# Tds_NonSmd_PRINT.net
KiCad netlist of a schematic drawn in EAGLE
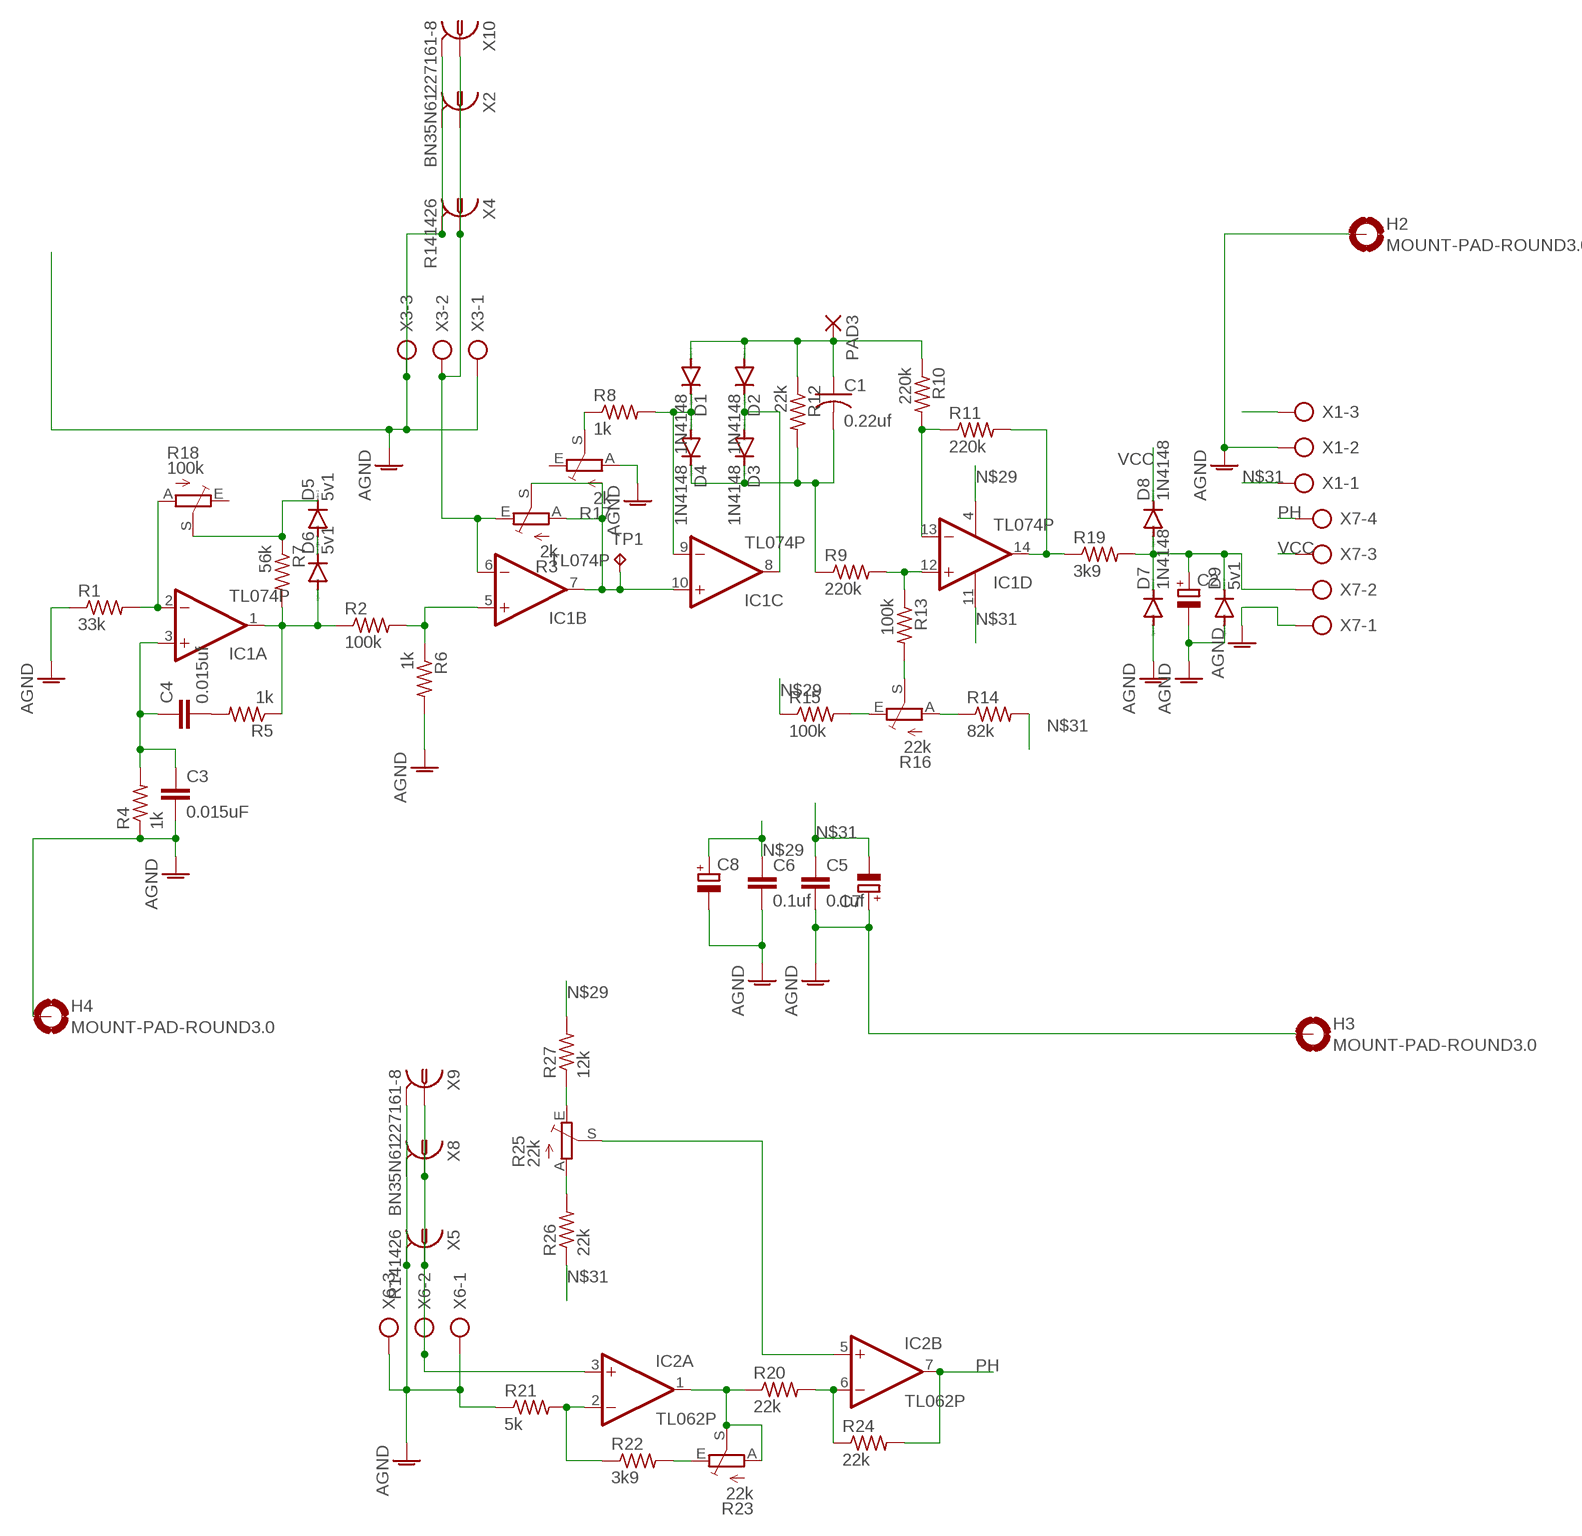
[diagram p0: schematic, sheet 1]

(export (version "E")
  (design (tool "Eeschema 10.0.6"))
  (components
    (comp (ref "C1")
      (value "0.22uf")
      (footprint "eagle-import:C050-024X044")
      (libsource (lib "eagle-import") (part "C-US050-024X044"))
    )
    (comp (ref "C2")
      (value "CPOL-EUE5-8.5")
      (footprint "eagle-import:E5-8,5")
      (libsource (lib "eagle-import") (part "CPOL-EUE5-8.5"))
    )
    (comp (ref "C3")
      (value "0.015uF")
      (footprint "eagle-import:C050-024X044")
      (libsource (lib "eagle-import") (part "C-EU050-024X044"))
    )
    (comp (ref "C4")
      (value "0.015uf")
      (footprint "eagle-import:C050-024X044")
      (libsource (lib "eagle-import") (part "C-EU050-024X044"))
    )
    (comp (ref "C5")
      (value "0.1uf")
      (footprint "eagle-import:C5B2.5")
      (libsource (lib "eagle-import") (part "C5/2.5"))
    )
    (comp (ref "C6")
      (value "0.1uf")
      (footprint "eagle-import:C5B2.5")
      (libsource (lib "eagle-import") (part "C5/2.5"))
    )
    (comp (ref "C7")
      (value "CPOL-EUE5-8.5")
      (footprint "eagle-import:E5-8,5")
      (libsource (lib "eagle-import") (part "CPOL-EUE5-8.5"))
    )
    (comp (ref "C8")
      (value "CPOL-EUE5-8.5")
      (footprint "eagle-import:E5-8,5")
      (libsource (lib "eagle-import") (part "CPOL-EUE5-8.5"))
    )
    (comp (ref "D1")
      (value "1N4148")
      (footprint "eagle-import:DO35-7")
      (libsource (lib "eagle-import") (part "1N4148DO35-7"))
    )
    (comp (ref "D2")
      (value "1N4148")
      (footprint "eagle-import:DO35-7")
      (libsource (lib "eagle-import") (part "1N4148DO35-7"))
    )
    (comp (ref "D3")
      (value "1N4148")
      (footprint "eagle-import:DO35-7")
      (libsource (lib "eagle-import") (part "1N4148DO35-7"))
    )
    (comp (ref "D4")
      (value "1N4148")
      (footprint "eagle-import:DO35-7")
      (libsource (lib "eagle-import") (part "1N4148DO35-7"))
    )
    (comp (ref "D5")
      (value "5v1")
      (footprint "eagle-import:DO35-7")
      (libsource (lib "eagle-import") (part "1N4148DO35-7"))
    )
    (comp (ref "D6")
      (value "5v1")
      (footprint "eagle-import:DO35-7")
      (libsource (lib "eagle-import") (part "1N4148DO35-7"))
    )
    (comp (ref "D7")
      (value "1N4148")
      (footprint "eagle-import:DO35-7")
      (libsource (lib "eagle-import") (part "1N4148DO35-7"))
    )
    (comp (ref "D8")
      (value "1N4148")
      (footprint "eagle-import:DO35-7")
      (libsource (lib "eagle-import") (part "1N4148DO35-7"))
    )
    (comp (ref "D9")
      (value "5v1")
      (footprint "eagle-import:DO35-7")
      (libsource (lib "eagle-import") (part "1N4148DO35-7"))
    )
    (comp (ref "H2")
      (value "MOUNT-PAD-ROUND3.0")
      (footprint "eagle-import:3,0-PAD")
      (libsource (lib "eagle-import") (part "MOUNT-PAD-ROUND3.0"))
    )
    (comp (ref "H3")
      (value "MOUNT-PAD-ROUND3.0")
      (footprint "eagle-import:3,0-PAD")
      (libsource (lib "eagle-import") (part "MOUNT-PAD-ROUND3.0"))
    )
    (comp (ref "H4")
      (value "MOUNT-PAD-ROUND3.0")
      (footprint "eagle-import:3,0-PAD")
      (libsource (lib "eagle-import") (part "MOUNT-PAD-ROUND3.0"))
    )
    (comp (ref "IC1")
      (value "TL074P")
      (footprint "eagle-import:DIL14")
      (libsource (lib "eagle-import") (part "TL074P"))
    )
    (comp (ref "IC2")
      (value "TL062P")
      (footprint "eagle-import:DIL08")
      (libsource (lib "eagle-import") (part "TL062P"))
    )
    (comp (ref "PAD3")
      (value "2,54/1,1")
      (footprint "eagle-import:2,54_1,1")
      (libsource (lib "eagle-import") (part "2,54/1,1"))
    )
    (comp (ref "R1")
      (value "33k")
      (footprint "eagle-import:0207_7")
      (libsource (lib "eagle-import") (part "resistor_348_R-US_0207/7"))
    )
    (comp (ref "R2")
      (value "100k")
      (footprint "eagle-import:0207_10")
      (libsource (lib "eagle-import") (part "R-US_0207/10"))
    )
    (comp (ref "R3")
      (value "2k")
      (footprint "eagle-import:S64W")
      (libsource (lib "eagle-import") (part "TRIM_EU-S64W"))
    )
    (comp (ref "R4")
      (value "1k")
      (footprint "eagle-import:0207_7")
      (libsource (lib "eagle-import") (part "resistor_348_R-US_0207/7"))
    )
    (comp (ref "R5")
      (value "1k")
      (footprint "eagle-import:0207_7")
      (libsource (lib "eagle-import") (part "resistor_348_R-US_0207/7"))
    )
    (comp (ref "R6")
      (value "1k")
      (footprint "eagle-import:0207_7")
      (libsource (lib "eagle-import") (part "resistor_348_R-US_0207/7"))
    )
    (comp (ref "R7")
      (value "56k")
      (footprint "eagle-import:0207_7")
      (libsource (lib "eagle-import") (part "resistor_348_R-US_0207/7"))
    )
    (comp (ref "R8")
      (value "1k")
      (footprint "eagle-import:0207_7")
      (libsource (lib "eagle-import") (part "resistor_348_R-US_0207/7"))
    )
    (comp (ref "R9")
      (value "220k")
      (footprint "eagle-import:0207_7")
      (libsource (lib "eagle-import") (part "resistor_348_R-US_0207/7"))
    )
    (comp (ref "R10")
      (value "220k")
      (footprint "eagle-import:0207_7")
      (libsource (lib "eagle-import") (part "resistor_348_R-US_0207/7"))
    )
    (comp (ref "R11")
      (value "220k")
      (footprint "eagle-import:0207_7")
      (libsource (lib "eagle-import") (part "resistor_348_R-US_0207/7"))
    )
    (comp (ref "R12")
      (value "22k")
      (footprint "eagle-import:0207_7")
      (libsource (lib "eagle-import") (part "resistor_348_R-US_0207/7"))
    )
    (comp (ref "R13")
      (value "100k")
      (footprint "eagle-import:0207_7")
      (libsource (lib "eagle-import") (part "resistor_348_R-US_0207/7"))
    )
    (comp (ref "R14")
      (value "82k")
      (footprint "eagle-import:0207_7")
      (libsource (lib "eagle-import") (part "resistor_348_R-US_0207/7"))
    )
    (comp (ref "R15")
      (value "100k")
      (footprint "eagle-import:0207_7")
      (libsource (lib "eagle-import") (part "resistor_348_R-US_0207/7"))
    )
    (comp (ref "R16")
      (value "22k")
      (footprint "eagle-import:S64W")
      (libsource (lib "eagle-import") (part "TRIM_EU-S64W"))
    )
    (comp (ref "R17")
      (value "2k")
      (footprint "eagle-import:S64W")
      (libsource (lib "eagle-import") (part "TRIM_EU-S64W"))
    )
    (comp (ref "R18")
      (value "100k")
      (footprint "eagle-import:S64W")
      (libsource (lib "eagle-import") (part "TRIM_EU-S64W"))
    )
    (comp (ref "R19")
      (value "3k9")
      (footprint "eagle-import:0207_7")
      (libsource (lib "eagle-import") (part "resistor_348_R-US_0207/7"))
    )
    (comp (ref "R20")
      (value "22k")
      (footprint "eagle-import:0207_7")
      (libsource (lib "eagle-import") (part "resistor_348_R-US_0207/7"))
    )
    (comp (ref "R21")
      (value "5k")
      (footprint "eagle-import:0207_7")
      (libsource (lib "eagle-import") (part "resistor_348_R-US_0207/7"))
    )
    (comp (ref "R22")
      (value "3k9")
      (footprint "eagle-import:0207_7")
      (libsource (lib "eagle-import") (part "resistor_348_R-US_0207/7"))
    )
    (comp (ref "R23")
      (value "22k")
      (footprint "eagle-import:S64W")
      (libsource (lib "eagle-import") (part "TRIM_EU-S64W"))
    )
    (comp (ref "R24")
      (value "22k")
      (footprint "eagle-import:0207_7")
      (libsource (lib "eagle-import") (part "resistor_348_R-US_0207/7"))
    )
    (comp (ref "R25")
      (value "22k")
      (footprint "eagle-import:S64W")
      (libsource (lib "eagle-import") (part "TRIM_EU-S64W"))
    )
    (comp (ref "R26")
      (value "22k")
      (footprint "eagle-import:0207_7")
      (libsource (lib "eagle-import") (part "resistor_348_R-US_0207/7"))
    )
    (comp (ref "R27")
      (value "12k")
      (footprint "eagle-import:0207_7")
      (libsource (lib "eagle-import") (part "resistor_348_R-US_0207/7"))
    )
    (comp (ref "TP1")
      (value "TPPAD1-13")
      (footprint "eagle-import:P1-13")
      (libsource (lib "eagle-import") (part "TPPAD1-13"))
    )
    (comp (ref "X1")
      (value "AK500/3")
      (footprint "eagle-import:AK500_3")
      (libsource (lib "eagle-import") (part "AK500/3"))
    )
    (comp (ref "X2")
      (value "BN35N61")
      (footprint "eagle-import:B35N61")
      (libsource (lib "eagle-import") (part "BN35N61"))
    )
    (comp (ref "X3")
      (value "AK500/3")
      (footprint "eagle-import:AK500_3")
      (libsource (lib "eagle-import") (part "AK500/3"))
    )
    (comp (ref "X4")
      (value "R141426")
      (footprint "eagle-import:R141426")
      (fields (field (name "MF") "FARNELL") (field (name "MPN") "R141426161"))
      (libsource (lib "eagle-import") (part "R141426"))
    )
    (comp (ref "X5")
      (value "R141426")
      (footprint "eagle-import:R141426")
      (fields (field (name "MF") "FARNELL") (field (name "MPN") "R141426161"))
      (libsource (lib "eagle-import") (part "R141426"))
    )
    (comp (ref "X6")
      (value "AK500/3")
      (footprint "eagle-import:AK500_3")
      (libsource (lib "eagle-import") (part "AK500/3"))
    )
    (comp (ref "X7")
      (value "AK500/4")
      (footprint "eagle-import:AK500_4")
      (libsource (lib "eagle-import") (part "AK500/4"))
    )
    (comp (ref "X8")
      (value "BN35N61")
      (footprint "eagle-import:B35N61")
      (libsource (lib "eagle-import") (part "BN35N61"))
    )
    (comp (ref "X9")
      (value "227161-8")
      (footprint "eagle-import:AMP_227161")
      (libsource (lib "eagle-import") (part "?227161-8"))
    )
    (comp (ref "X10")
      (value "227161-8")
      (footprint "eagle-import:AMP_227161")
      (libsource (lib "eagle-import") (part "?227161-8"))
    )
  )
  (nets
    (net (code "1") (name "/N$29") (class "Default")
      (node (ref "C6") (pin "1") (pinfunction "1_1") (pintype "passive"))
      (node (ref "C8") (pin "+") (pinfunction "+_+") (pintype "passive"))
      (node (ref "IC1") (pin "4") (pinfunction "V+_4") (pintype "power_in"))
      (node (ref "R15") (pin "1") (pinfunction "1_1") (pintype "passive"))
      (node (ref "R27") (pin "2") (pinfunction "2_2") (pintype "passive"))
      (node (ref "X1") (pin "3") (pinfunction "KL_3") (pintype "passive"))
    )
    (net (code "2") (name "/N$31") (class "Default")
      (node (ref "C5") (pin "1") (pinfunction "1_1") (pintype "passive"))
      (node (ref "C7") (pin "-") (pinfunction "-_-") (pintype "passive"))
      (node (ref "IC1") (pin "11") (pinfunction "V-_11") (pintype "power_in"))
      (node (ref "R14") (pin "2") (pinfunction "2_2") (pintype "passive"))
      (node (ref "R26") (pin "1") (pinfunction "1_1") (pintype "passive"))
      (node (ref "X1") (pin "1") (pinfunction "KL_1") (pintype "passive"))
    )
    (net (code "3") (name "/PH") (class "Default")
      (node (ref "IC2") (pin "7") (pinfunction "OUT_7") (pintype "output"))
      (node (ref "R24") (pin "2") (pinfunction "2_2") (pintype "passive"))
      (node (ref "X7") (pin "4") (pinfunction "KL_4") (pintype "passive"))
    )
    (net (code "4") (name "/VCC") (class "Default")
      (node (ref "D8") (pin "C") (pinfunction "C_C") (pintype "passive"))
      (node (ref "X7") (pin "3") (pinfunction "KL_3") (pintype "passive"))
    )
    (net (code "5") (name "AGND") (class "Default")
      (node (ref "C2") (pin "-") (pinfunction "-_-") (pintype "passive"))
      (node (ref "C3") (pin "2") (pinfunction "2_2") (pintype "passive"))
      (node (ref "C5") (pin "2") (pinfunction "2_2") (pintype "passive"))
      (node (ref "C6") (pin "2") (pinfunction "2_2") (pintype "passive"))
      (node (ref "C7") (pin "+") (pinfunction "+_+") (pintype "passive"))
      (node (ref "C8") (pin "-") (pinfunction "-_-") (pintype "passive"))
      (node (ref "D7") (pin "A") (pinfunction "A_A") (pintype "passive"))
      (node (ref "D9") (pin "A") (pinfunction "A_A") (pintype "passive"))
      (node (ref "H2") (pin "B3,0") (pinfunction "MOUNT_B3,0") (pintype "passive"))
      (node (ref "H3") (pin "B3,0") (pinfunction "MOUNT_B3,0") (pintype "passive"))
      (node (ref "H4") (pin "B3,0") (pinfunction "MOUNT_B3,0") (pintype "passive"))
      (node (ref "R1") (pin "1") (pinfunction "1_1") (pintype "passive"))
      (node (ref "R17") (pin "A") (pinfunction "A_A") (pintype "passive"))
      (node (ref "R21") (pin "1") (pinfunction "1_1") (pintype "passive"))
      (node (ref "R4") (pin "1") (pinfunction "1_1") (pintype "passive"))
      (node (ref "R6") (pin "2") (pinfunction "2_2") (pintype "passive"))
      (node (ref "X1") (pin "2") (pinfunction "KL_2") (pintype "passive"))
      (node (ref "X10") (pin "2") (pinfunction "2_2") (pintype "passive"))
      (node (ref "X2") (pin "2") (pinfunction "2_2") (pintype "passive"))
      (node (ref "X2") (pin "3") (pinfunction "2_3") (pintype "passive"))
      (node (ref "X2") (pin "4") (pinfunction "2_4") (pintype "passive"))
      (node (ref "X2") (pin "5") (pinfunction "2_5") (pintype "passive"))
      (node (ref "X3") (pin "1") (pinfunction "KL_1") (pintype "passive"))
      (node (ref "X3") (pin "3") (pinfunction "KL_3") (pintype "passive"))
      (node (ref "X4") (pin "2") (pinfunction "2_2") (pintype "passive"))
      (node (ref "X4") (pin "3") (pinfunction "2_3") (pintype "passive"))
      (node (ref "X4") (pin "4") (pinfunction "2_4") (pintype "passive"))
      (node (ref "X4") (pin "5") (pinfunction "2_5") (pintype "passive"))
      (node (ref "X5") (pin "2") (pinfunction "2_2") (pintype "passive"))
      (node (ref "X5") (pin "3") (pinfunction "2_3") (pintype "passive"))
      (node (ref "X5") (pin "4") (pinfunction "2_4") (pintype "passive"))
      (node (ref "X5") (pin "5") (pinfunction "2_5") (pintype "passive"))
      (node (ref "X6") (pin "1") (pinfunction "KL_1") (pintype "passive"))
      (node (ref "X6") (pin "3") (pinfunction "KL_3") (pintype "passive"))
      (node (ref "X7") (pin "1") (pinfunction "KL_1") (pintype "passive"))
      (node (ref "X8") (pin "2") (pinfunction "2_2") (pintype "passive"))
      (node (ref "X8") (pin "3") (pinfunction "2_3") (pintype "passive"))
      (node (ref "X8") (pin "4") (pinfunction "2_4") (pintype "passive"))
      (node (ref "X8") (pin "5") (pinfunction "2_5") (pintype "passive"))
      (node (ref "X9") (pin "2") (pinfunction "2_2") (pintype "passive"))
    )
    (net (code "6") (name "Net-(C1-Pad2)") (class "Default")
      (node (ref "C1") (pin "2") (pinfunction "2_2") (pintype "passive"))
      (node (ref "D3") (pin "C") (pinfunction "C_C") (pintype "passive"))
      (node (ref "D4") (pin "C") (pinfunction "C_C") (pintype "passive"))
      (node (ref "R12") (pin "2") (pinfunction "2_2") (pintype "passive"))
      (node (ref "R9") (pin "1") (pinfunction "1_1") (pintype "passive"))
    )
    (net (code "7") (name "Net-(C4-Pad2)") (class "Default")
      (node (ref "C4") (pin "2") (pinfunction "2_2") (pintype "passive"))
      (node (ref "R5") (pin "2") (pinfunction "2_2") (pintype "passive"))
    )
    (net (code "8") (name "Net-(D5-PadA)") (class "Default")
      (node (ref "D5") (pin "A") (pinfunction "A_A") (pintype "passive"))
      (node (ref "D6") (pin "C") (pinfunction "C_C") (pintype "passive"))
    )
    (net (code "9") (name "Net-(D5-PadC)") (class "Default")
      (node (ref "D5") (pin "C") (pinfunction "C_C") (pintype "passive"))
      (node (ref "R18") (pin "S") (pinfunction "S_S") (pintype "passive"))
      (node (ref "R7") (pin "1") (pinfunction "1_1") (pintype "passive"))
    )
    (net (code "10") (name "Net-(IC1A-+IN)") (class "Default")
      (node (ref "C3") (pin "1") (pinfunction "1_1") (pintype "passive"))
      (node (ref "C4") (pin "1") (pinfunction "1_1") (pintype "passive"))
      (node (ref "IC1") (pin "3") (pinfunction "+IN_3") (pintype "input"))
      (node (ref "R4") (pin "2") (pinfunction "2_2") (pintype "passive"))
    )
    (net (code "11") (name "Net-(IC1A--IN)") (class "Default")
      (node (ref "IC1") (pin "2") (pinfunction "-IN_2") (pintype "input"))
      (node (ref "R1") (pin "2") (pinfunction "2_2") (pintype "passive"))
      (node (ref "R18") (pin "A") (pinfunction "A_A") (pintype "passive"))
    )
    (net (code "12") (name "Net-(IC1A-OUT)") (class "Default")
      (node (ref "D6") (pin "A") (pinfunction "A_A") (pintype "passive"))
      (node (ref "IC1") (pin "1") (pinfunction "OUT_1") (pintype "output"))
      (node (ref "R2") (pin "1") (pinfunction "1_1") (pintype "passive"))
      (node (ref "R5") (pin "1") (pinfunction "1_1") (pintype "passive"))
      (node (ref "R7") (pin "2") (pinfunction "2_2") (pintype "passive"))
    )
    (net (code "13") (name "Net-(IC1B-+IN)") (class "Default")
      (node (ref "IC1") (pin "5") (pinfunction "+IN_5") (pintype "input"))
      (node (ref "R2") (pin "2") (pinfunction "2_2") (pintype "passive"))
      (node (ref "R6") (pin "1") (pinfunction "1_1") (pintype "passive"))
    )
    (net (code "14") (name "Net-(IC1B--IN)") (class "Default")
      (node (ref "IC1") (pin "6") (pinfunction "-IN_6") (pintype "input"))
      (node (ref "R3") (pin "E") (pinfunction "E_E") (pintype "passive"))
      (node (ref "X10") (pin "1") (pinfunction "1_1") (pintype "passive"))
      (node (ref "X2") (pin "1") (pinfunction "1_1") (pintype "passive"))
      (node (ref "X3") (pin "2") (pinfunction "KL_2") (pintype "passive"))
      (node (ref "X4") (pin "1") (pinfunction "1_1") (pintype "passive"))
    )
    (net (code "15") (name "Net-(IC1B-OUT)") (class "Default")
      (node (ref "IC1") (pin "10") (pinfunction "+IN_10") (pintype "input"))
      (node (ref "IC1") (pin "7") (pinfunction "OUT_7") (pintype "output"))
      (node (ref "R3") (pin "A") (pinfunction "A_A") (pintype "passive"))
      (node (ref "R3") (pin "S") (pinfunction "S_S") (pintype "passive"))
      (node (ref "TP1") (pin "TP") (pinfunction "TP_TP") (pintype "input"))
    )
    (net (code "16") (name "Net-(IC1C--IN)") (class "Default")
      (node (ref "D1") (pin "C") (pinfunction "C_C") (pintype "passive"))
      (node (ref "D4") (pin "A") (pinfunction "A_A") (pintype "passive"))
      (node (ref "IC1") (pin "9") (pinfunction "-IN_9") (pintype "input"))
      (node (ref "R8") (pin "2") (pinfunction "2_2") (pintype "passive"))
    )
    (net (code "17") (name "Net-(IC1C-OUT)") (class "Default")
      (node (ref "D2") (pin "C") (pinfunction "C_C") (pintype "passive"))
      (node (ref "D3") (pin "A") (pinfunction "A_A") (pintype "passive"))
      (node (ref "IC1") (pin "8") (pinfunction "OUT_8") (pintype "output"))
    )
    (net (code "18") (name "Net-(IC1D-+IN)") (class "Default")
      (node (ref "IC1") (pin "12") (pinfunction "+IN_12") (pintype "input"))
      (node (ref "R13") (pin "1") (pinfunction "1_1") (pintype "passive"))
      (node (ref "R9") (pin "2") (pinfunction "2_2") (pintype "passive"))
    )
    (net (code "19") (name "Net-(IC1D--IN)") (class "Default")
      (node (ref "IC1") (pin "13") (pinfunction "-IN_13") (pintype "input"))
      (node (ref "R10") (pin "2") (pinfunction "2_2") (pintype "passive"))
      (node (ref "R11") (pin "1") (pinfunction "1_1") (pintype "passive"))
    )
    (net (code "20") (name "Net-(IC1D-OUT)") (class "Default")
      (node (ref "IC1") (pin "14") (pinfunction "OUT_14") (pintype "output"))
      (node (ref "R11") (pin "2") (pinfunction "2_2") (pintype "passive"))
      (node (ref "R19") (pin "1") (pinfunction "1_1") (pintype "passive"))
    )
    (net (code "21") (name "Net-(IC2A-+IN)") (class "Default")
      (node (ref "IC2") (pin "3") (pinfunction "+IN_3") (pintype "input"))
      (node (ref "X5") (pin "1") (pinfunction "1_1") (pintype "passive"))
      (node (ref "X6") (pin "2") (pinfunction "KL_2") (pintype "passive"))
      (node (ref "X8") (pin "1") (pinfunction "1_1") (pintype "passive"))
      (node (ref "X9") (pin "1") (pinfunction "1_1") (pintype "passive"))
    )
    (net (code "22") (name "Net-(IC2A--IN)") (class "Default")
      (node (ref "IC2") (pin "2") (pinfunction "-IN_2") (pintype "input"))
      (node (ref "R21") (pin "2") (pinfunction "2_2") (pintype "passive"))
      (node (ref "R22") (pin "1") (pinfunction "1_1") (pintype "passive"))
    )
    (net (code "23") (name "Net-(IC2A-OUT)") (class "Default")
      (node (ref "IC2") (pin "1") (pinfunction "OUT_1") (pintype "output"))
      (node (ref "R20") (pin "1") (pinfunction "1_1") (pintype "passive"))
      (node (ref "R23") (pin "A") (pinfunction "A_A") (pintype "passive"))
      (node (ref "R23") (pin "S") (pinfunction "S_S") (pintype "passive"))
    )
    (net (code "24") (name "Net-(IC2B-+IN)") (class "Default")
      (node (ref "IC2") (pin "5") (pinfunction "+IN_5") (pintype "input"))
      (node (ref "R25") (pin "S") (pinfunction "S_S") (pintype "passive"))
    )
    (net (code "25") (name "Net-(IC2B--IN)") (class "Default")
      (node (ref "IC2") (pin "6") (pinfunction "-IN_6") (pintype "input"))
      (node (ref "R20") (pin "2") (pinfunction "2_2") (pintype "passive"))
      (node (ref "R24") (pin "1") (pinfunction "1_1") (pintype "passive"))
    )
    (net (code "26") (name "Net-(PAD3-P)") (class "Default")
      (node (ref "C1") (pin "1") (pinfunction "1_1") (pintype "passive"))
      (node (ref "D1") (pin "A") (pinfunction "A_A") (pintype "passive"))
      (node (ref "D2") (pin "A") (pinfunction "A_A") (pintype "passive"))
      (node (ref "PAD3") (pin "1") (pinfunction "P_1") (pintype "passive"))
      (node (ref "R10") (pin "1") (pinfunction "1_1") (pintype "passive"))
      (node (ref "R12") (pin "1") (pinfunction "1_1") (pintype "passive"))
    )
    (net (code "27") (name "Net-(R13-Pad2)") (class "Default")
      (node (ref "R13") (pin "2") (pinfunction "2_2") (pintype "passive"))
      (node (ref "R16") (pin "S") (pinfunction "S_S") (pintype "passive"))
    )
    (net (code "28") (name "Net-(R14-Pad1)") (class "Default")
      (node (ref "R14") (pin "1") (pinfunction "1_1") (pintype "passive"))
      (node (ref "R16") (pin "A") (pinfunction "A_A") (pintype "passive"))
    )
    (net (code "29") (name "Net-(R15-Pad2)") (class "Default")
      (node (ref "R15") (pin "2") (pinfunction "2_2") (pintype "passive"))
      (node (ref "R16") (pin "E") (pinfunction "E_E") (pintype "passive"))
    )
    (net (code "30") (name "Net-(R17-PadS)") (class "Default")
      (node (ref "R17") (pin "S") (pinfunction "S_S") (pintype "passive"))
      (node (ref "R8") (pin "1") (pinfunction "1_1") (pintype "passive"))
    )
    (net (code "31") (name "Net-(R22-Pad2)") (class "Default")
      (node (ref "R22") (pin "2") (pinfunction "2_2") (pintype "passive"))
      (node (ref "R23") (pin "E") (pinfunction "E_E") (pintype "passive"))
    )
    (net (code "32") (name "Net-(R25-PadA)") (class "Default")
      (node (ref "R25") (pin "A") (pinfunction "A_A") (pintype "passive"))
      (node (ref "R26") (pin "2") (pinfunction "2_2") (pintype "passive"))
    )
    (net (code "33") (name "Net-(R25-PadE)") (class "Default")
      (node (ref "R25") (pin "E") (pinfunction "E_E") (pintype "passive"))
      (node (ref "R27") (pin "1") (pinfunction "1_1") (pintype "passive"))
    )
    (net (code "34") (name "Net-(X7B-KL)") (class "Default")
      (node (ref "C2") (pin "+") (pinfunction "+_+") (pintype "passive"))
      (node (ref "D7") (pin "C") (pinfunction "C_C") (pintype "passive"))
      (node (ref "D8") (pin "A") (pinfunction "A_A") (pintype "passive"))
      (node (ref "D9") (pin "C") (pinfunction "C_C") (pintype "passive"))
      (node (ref "R19") (pin "2") (pinfunction "2_2") (pintype "passive"))
      (node (ref "X7") (pin "2") (pinfunction "KL_2") (pintype "passive"))
    )
    (net (code "35") (name "unconnected-(R17-PadE)") (class "Default")
      (node (ref "R17") (pin "E") (pinfunction "E_E") (pintype "passive"))
    )
    (net (code "36") (name "unconnected-(R18-PadE)") (class "Default")
      (node (ref "R18") (pin "E") (pinfunction "E_E") (pintype "passive"))
    )
  )
)
